# ltc1474_400mA.net
KiCad netlist of a schematic drawn in Altium Designer
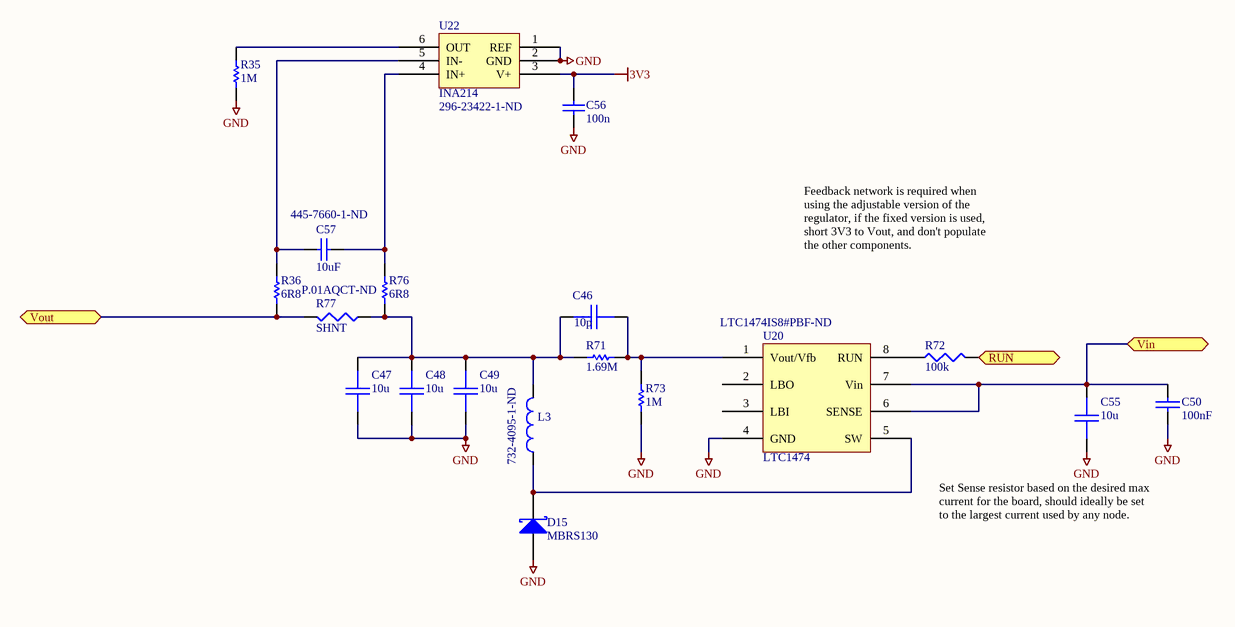
[diagram p0: ltc1474_400mA.SchDoc]

(export (version "E")
  (design (tool "Eeschema 10.0.6"))
  (components
    (comp (ref "C46")
      (value "10p")
      (footprint "0603")
      (description "Capacitor")
      (fields
        (field (name "MANUFACTURER") "TDK Corporation")
        (field (name "MANUFACTURER PART NUMBER") "C1608C0G1H100D080AA")
      )
      (libsource (lib "Miscellaneous Devices") (part "CAP"))
    )
    (comp (ref "C47")
      (value "10u")
      (footprint "1206")
      (description "Capacitor")
      (fields
        (field (name "MANUFACTURER") "TDK Corporation")
        (field (name "MANUFACTURER PART NUMBER") "C3216X5R1A106M160AB")
      )
      (libsource (lib "RCLDQ") (part "CAP"))
    )
    (comp (ref "C48")
      (value "10u")
      (footprint "1206")
      (description "Capacitor")
      (fields
        (field (name "MANUFACTURER") "TDK Corporation")
        (field (name "MANUFACTURER PART NUMBER") "C3216X5R1A106M160AB")
      )
      (libsource (lib "RCLDQ") (part "CAP"))
    )
    (comp (ref "C49")
      (value "10u")
      (footprint "1206")
      (description "Capacitor")
      (fields
        (field (name "MANUFACTURER") "TDK Corporation")
        (field (name "MANUFACTURER PART NUMBER") "C3216X5R1A106M160AB")
      )
      (libsource (lib "RCLDQ") (part "CAP"))
    )
    (comp (ref "C50")
      (value "100nF")
      (footprint "0603")
      (description "Capacitor")
      (fields
        (field (name "MANUFACTURER") "TDK Corporation")
        (field (name "MANUFACTURER PART NUMBER") "C1608X7R1H103K080AA")
      )
      (libsource (lib "*") (part "CAP"))
    )
    (comp (ref "C55")
      (value "10u")
      (footprint "1206")
      (description "Capacitor")
      (fields
        (field (name "MANUFACTURER") "TDK Corporation")
        (field (name "MANUFACTURER PART NUMBER") "C3216X5R1A106M160AB")
      )
      (libsource (lib "RCLDQ") (part "CAP"))
    )
    (comp (ref "C56")
      (value "100n")
      (footprint "0603")
      (description "Capacitor (Semiconductor SIM Model)")
      (fields (field (name "PUBLISHER") "Altium Limited"))
      (libsource (lib "Miscellaneous Devices") (part "Cap Semi"))
    )
    (comp (ref "C57")
      (value "10uF")
      (footprint "0805")
      (description "Capacitor (Semiconductor SIM Model)")
      (fields
        (field (name "SUPPLIER PART NUMBER 1") "445-7660-1-ND")
        (field (name "MANUFACTURER") "TDK Corporation")
        (field (name "MANUFACTURER PART NUMBER") "C2012X5R1A106K125AB")
      )
      (libsource (lib "Miscellaneous Devices") (part "Cap Semi"))
    )
    (comp (ref "D15")
      (value "MBRS130")
      (footprint "SMB")
      (description "Schottky Diode")
      (fields
        (field (name "MANUFACTURER") "Fairchild Semiconductor")
        (field (name "MANUFACTURER PART NUMBER") "MBRS130L")
      )
      (libsource (lib "RCLDQ") (part "D SCHOTTKY"))
    )
    (comp (ref "L3")
      (value "INDUCTOR")
      (footprint "WE-TPC-744065221")
      (description "INDUCTOR POWER 220UH .50A SMD")
      (fields
        (field (name "SUPPLIER PART NUMBER 1") "732-4095-1-ND")
        (field (name "MANUFACTURER") "Wurth Electronics Inc")
        (field (name "MANUFACTURER PART NUMBER") "744065221")
      )
      (libsource (lib "steve") (part "INDUCTOR"))
    )
    (comp (ref "R35")
      (value "1M")
      (footprint "0603")
      (description "Semiconductor Resistor")
      (fields
        (field (name "MANUFACTURER") "Panasonic Electronic Components")
        (field (name "MANUFACTURER PART NUMBER") "ERJ-3EKF1004V")
        (field (name "PUBLISHER") "Altium Limited")
      )
      (libsource (lib "Miscellaneous Devices") (part "Res Semi"))
    )
    (comp (ref "R36")
      (value "6R8")
      (footprint "0603")
      (description "Semiconductor Resistor")
      (fields
        (field (name "MANUFACTURER") "Panasonic Electronic Components")
        (field (name "MANUFACTURER PART NUMBER") "ERJ-3GEYJ6R8V")
        (field (name "PUBLISHER") "Altium Limited")
      )
      (libsource (lib "Miscellaneous Devices") (part "Res Semi"))
    )
    (comp (ref "R71")
      (value "1.69M")
      (footprint "0603")
      (description "Semiconductor Resistor")
      (fields
        (field (name "MANUFACTURER") "Samsung Electro-Mechanics America, Inc")
        (field (name "MANUFACTURER PART NUMBER") "RC1608F1694CS")
        (field (name "PUBLISHER") "Altium Limited")
      )
      (libsource (lib "Miscellaneous Devices") (part "Res Semi"))
    )
    (comp (ref "R72")
      (value "100k")
      (footprint "0603")
      (description "Resistor")
      (fields
        (field (name "MANUFACTURER") "Panasonic Electronic Components")
        (field (name "MANUFACTURER PART NUMBER") "ERJ-3EKF1003V")
      )
      (libsource (lib "RCLDQ") (part "RES1"))
    )
    (comp (ref "R73")
      (value "1M")
      (footprint "0603")
      (description "Semiconductor Resistor")
      (fields
        (field (name "MANUFACTURER") "Panasonic Electronic Components")
        (field (name "MANUFACTURER PART NUMBER") "ERJ-3EKF1004V")
        (field (name "PUBLISHER") "Altium Limited")
      )
      (libsource (lib "Miscellaneous Devices") (part "Res Semi"))
    )
    (comp (ref "R76")
      (value "6R8")
      (footprint "0603")
      (description "Semiconductor Resistor")
      (fields
        (field (name "MANUFACTURER") "Panasonic Electronic Components")
        (field (name "MANUFACTURER PART NUMBER") "ERJ-3GEYJ6R8V")
        (field (name "PUBLISHER") "Altium Limited")
      )
      (libsource (lib "Miscellaneous Devices") (part "Res Semi"))
    )
    (comp (ref "R77")
      (value "SHNT")
      (footprint "0805")
      (description "Resistor")
      (fields
        (field (name "SUPPLIER PART NUMBER 1") "P.01AQCT-ND")
        (field (name "MANUFACTURER") "Panasonic Electronic Components")
        (field (name "MANUFACTURER PART NUMBER") "ERJ-6BWFR010V")
        (field (name "PUBLISHER") "Altium Limited")
      )
      (libsource (lib "Miscellaneous Devices") (part "Res3"))
    )
    (comp (ref "U20")
      (value "LTC1474")
      (footprint "SO8")
      (description "Step-down converter")
      (fields
        (field (name "SUPPLIER PART NUMBER 1") "LTC1474IS8#PBF-ND")
        (field (name "MANUFACTURER") "Linear Technology")
        (field (name "MANUFACTURER PART NUMBER") "LTC1474IS8#PBF")
      )
      (libsource (lib "MiscellaneousIC") (part "LTC1474"))
    )
    (comp (ref "U22")
      (value "INA214")
      (footprint "SC70-6")
      (description "Current Shunt Monitor")
      (fields
        (field (name "SUPPLIER PART NUMBER 1") "296-23422-1-ND")
        (field (name "MANUFACTURER") "Texas Instruments")
        (field (name "MANUFACTURER PART NUMBER") "INA214AIDCKT")
      )
      (libsource (lib "MiscellaneousIC") (part "ina214"))
    )
  )
  (nets
    (net (code "1") (name "/RUN") (class "Default")
      (node (ref "R72") (pin "2") (pinfunction "2_2") (pintype "passive"))
    )
    (net (code "2") (name "/Vin") (class "Default")
      (node (ref "C50") (pin "1") (pinfunction "1_1") (pintype "passive"))
      (node (ref "C55") (pin "1") (pinfunction "1_1") (pintype "passive"))
      (node (ref "U20") (pin "6") (pinfunction "SENSE_6") (pintype "passive"))
      (node (ref "U20") (pin "7") (pinfunction "Vin_7") (pintype "passive"))
    )
    (net (code "3") (name "/Vout") (class "Default")
      (node (ref "R36") (pin "2") (pinfunction "2_2") (pintype "passive"))
      (node (ref "R77") (pin "2") (pinfunction "2_2") (pintype "passive"))
    )
    (net (code "4") (name "3V3") (class "Default")
      (node (ref "C56") (pin "2") (pinfunction "2_2") (pintype "passive"))
      (node (ref "U22") (pin "3") (pinfunction "V+_3") (pintype "power_in"))
    )
    (net (code "5") (name "GND") (class "Default")
      (node (ref "C47") (pin "2") (pinfunction "2_2") (pintype "passive"))
      (node (ref "C48") (pin "2") (pinfunction "2_2") (pintype "passive"))
      (node (ref "C49") (pin "2") (pinfunction "2_2") (pintype "passive"))
      (node (ref "C50") (pin "2") (pinfunction "2_2") (pintype "passive"))
      (node (ref "C55") (pin "2") (pinfunction "2_2") (pintype "passive"))
      (node (ref "C56") (pin "1") (pinfunction "1_1") (pintype "passive"))
      (node (ref "D15") (pin "A") (pinfunction "A_A") (pintype "passive"))
      (node (ref "R35") (pin "1") (pinfunction "1_1") (pintype "passive"))
      (node (ref "R73") (pin "1") (pinfunction "1_1") (pintype "passive"))
      (node (ref "U20") (pin "4") (pinfunction "GND_4") (pintype "passive"))
      (node (ref "U22") (pin "1") (pinfunction "REF_1") (pintype "power_in"))
      (node (ref "U22") (pin "2") (pinfunction "GND_2") (pintype "power_in"))
    )
    (net (code "6") (name "Net-(C46-Pad1)") (class "Default")
      (node (ref "C46") (pin "1") (pinfunction "1_1") (pintype "passive"))
      (node (ref "C47") (pin "1") (pinfunction "1_1") (pintype "passive"))
      (node (ref "C48") (pin "1") (pinfunction "1_1") (pintype "passive"))
      (node (ref "C49") (pin "1") (pinfunction "1_1") (pintype "passive"))
      (node (ref "L3") (pin "2") (pinfunction "2_2") (pintype "passive"))
      (node (ref "R71") (pin "1") (pinfunction "1_1") (pintype "passive"))
      (node (ref "R76") (pin "2") (pinfunction "2_2") (pintype "passive"))
      (node (ref "R77") (pin "1") (pinfunction "1_1") (pintype "passive"))
    )
    (net (code "7") (name "Net-(U20-RUN)") (class "Default")
      (node (ref "R72") (pin "1") (pinfunction "1_1") (pintype "passive"))
      (node (ref "U20") (pin "8") (pinfunction "RUN_8") (pintype "passive"))
    )
    (net (code "8") (name "Net-(U20-SW)") (class "Default")
      (node (ref "D15") (pin "K") (pinfunction "K_K") (pintype "passive"))
      (node (ref "L3") (pin "1") (pinfunction "1_1") (pintype "passive"))
      (node (ref "U20") (pin "5") (pinfunction "SW_5") (pintype "passive"))
    )
    (net (code "9") (name "Net-(U20-Vout{slash}Vfb)") (class "Default")
      (node (ref "C46") (pin "2") (pinfunction "2_2") (pintype "passive"))
      (node (ref "R71") (pin "2") (pinfunction "2_2") (pintype "passive"))
      (node (ref "R73") (pin "2") (pinfunction "2_2") (pintype "passive"))
      (node (ref "U20") (pin "1") (pinfunction "Vout/Vfb_1") (pintype "passive"))
    )
    (net (code "10") (name "Net-(U22-IN+)") (class "Default")
      (node (ref "C57") (pin "2") (pinfunction "2_2") (pintype "passive"))
      (node (ref "R76") (pin "1") (pinfunction "1_1") (pintype "passive"))
      (node (ref "U22") (pin "4") (pinfunction "IN+_4") (pintype "power_in"))
    )
    (net (code "11") (name "Net-(U22-IN-)") (class "Default")
      (node (ref "C57") (pin "1") (pinfunction "1_1") (pintype "passive"))
      (node (ref "R36") (pin "1") (pinfunction "1_1") (pintype "passive"))
      (node (ref "U22") (pin "5") (pinfunction "IN-_5") (pintype "power_in"))
    )
    (net (code "12") (name "Net-(U22-OUT)") (class "Default")
      (node (ref "R35") (pin "2") (pinfunction "2_2") (pintype "passive"))
      (node (ref "U22") (pin "6") (pinfunction "OUT_6") (pintype "power_in"))
    )
    (net (code "13") (name "unconnected-(U20-LBI-Pad3)") (class "Default")
      (node (ref "U20") (pin "3") (pinfunction "LBI_3") (pintype "passive"))
    )
    (net (code "14") (name "unconnected-(U20-LBO-Pad2)") (class "Default")
      (node (ref "U20") (pin "2") (pinfunction "LBO_2") (pintype "passive"))
    )
  )
)
